# SparkFun_GPS_NEO_M9N_uFL.net
KiCad netlist of a schematic drawn in EAGLE
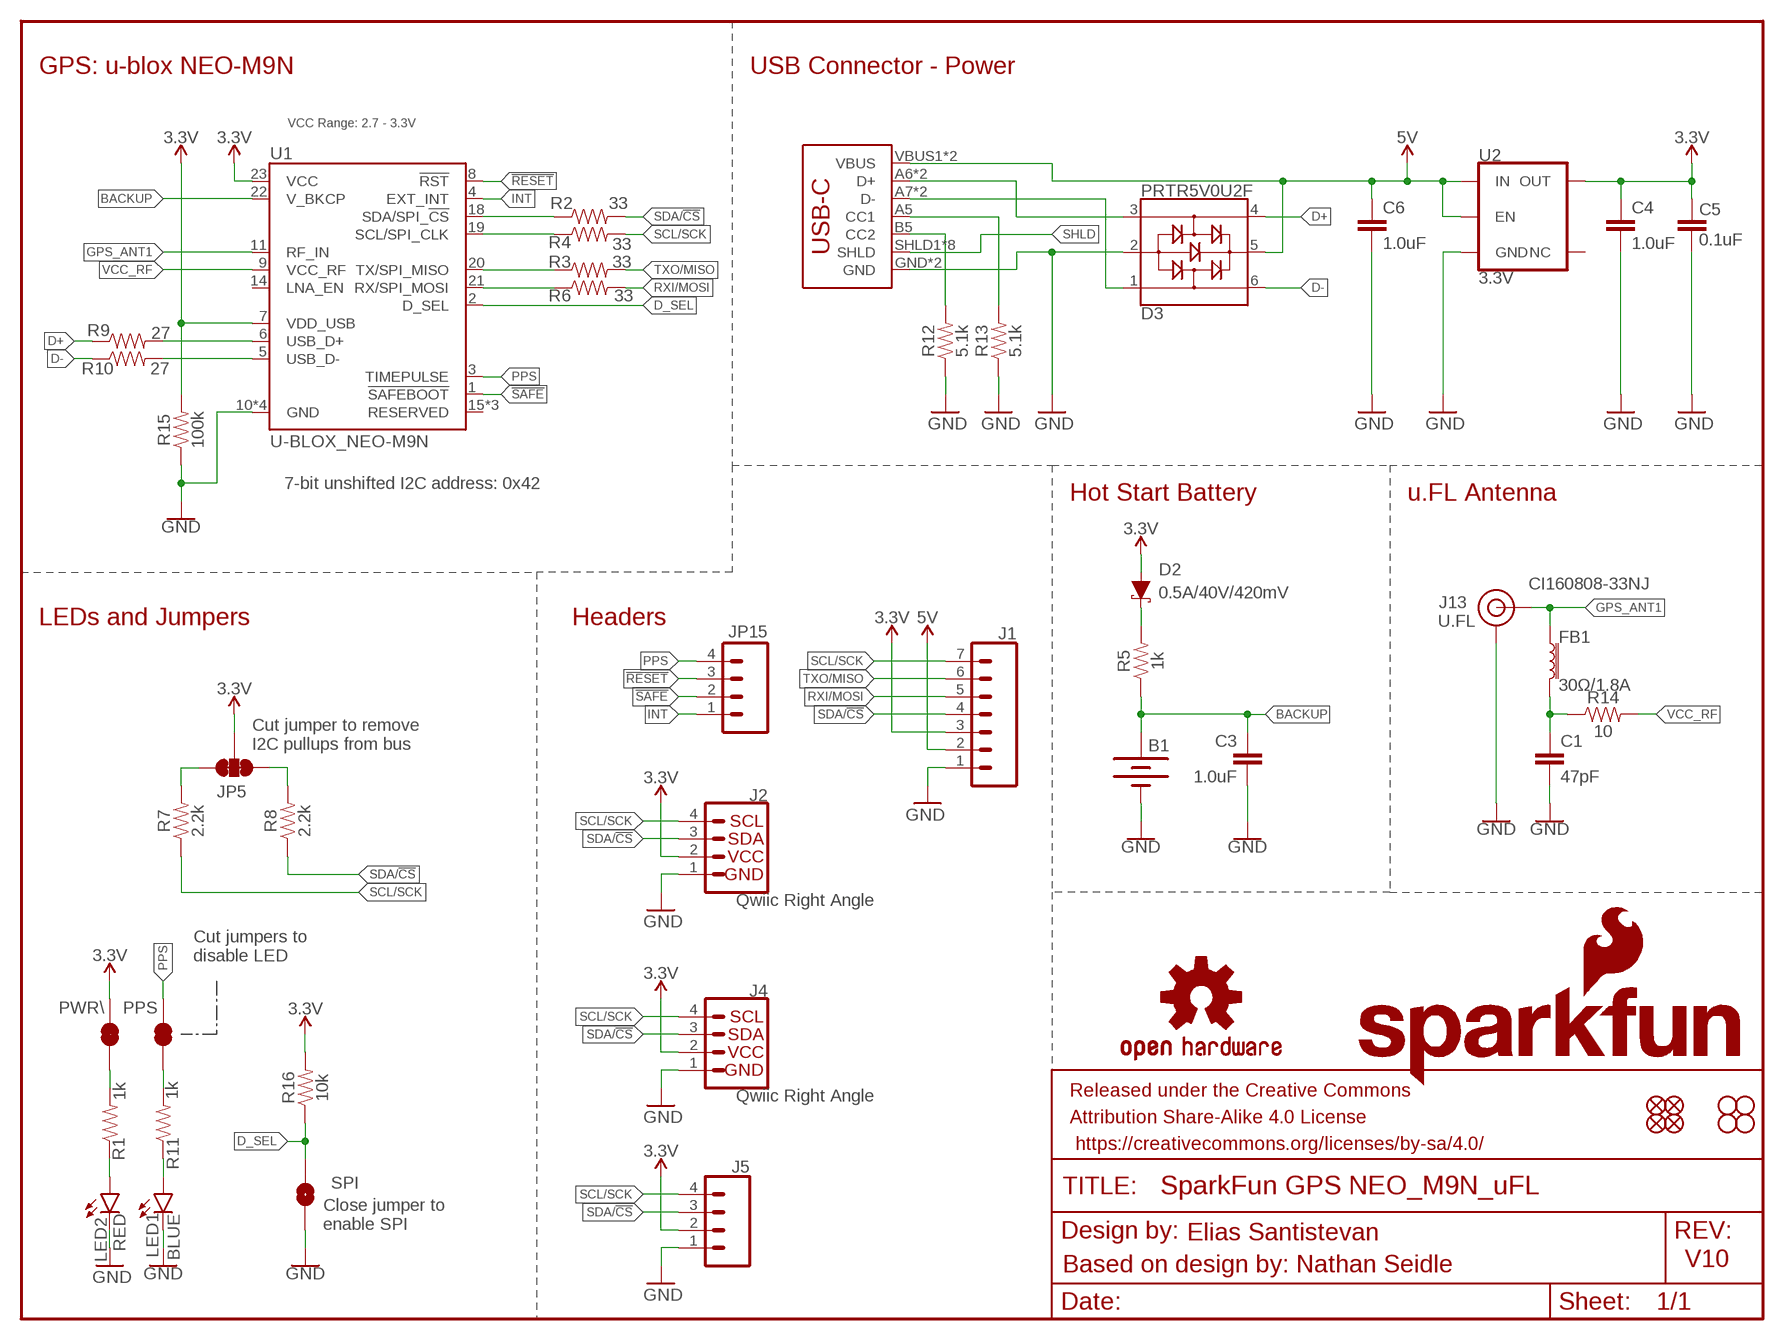
[diagram p0: schematic, sheet 1]

(export (version "E")
  (design (tool "Eeschema 10.0.6"))
  (components
    (comp (ref "B1")
      (value "6.8MM_COIN_CELL")
      (footprint "eagle-import:ML414H_IV01E")
      (libsource (lib "eagle-import") (part "ML414H_IV01E_BATTERY"))
    )
    (comp (ref "C1")
      (value "47pF")
      (footprint "eagle-import:0603")
      (libsource (lib "eagle-import") (part "47PF-0603-50V-5%"))
    )
    (comp (ref "C3")
      (value "1.0uF")
      (footprint "eagle-import:0603")
      (libsource (lib "eagle-import") (part "1.0UF-0603-16V-10%"))
    )
    (comp (ref "C4")
      (value "1.0uF")
      (footprint "eagle-import:0603")
      (libsource (lib "eagle-import") (part "1.0UF-0603-16V-10%"))
    )
    (comp (ref "C5")
      (value "0.1uF")
      (footprint "eagle-import:0603")
      (libsource (lib "eagle-import") (part "0.1UF-0603-25V-(+80/-20%)"))
    )
    (comp (ref "C6")
      (value "1.0uF")
      (footprint "eagle-import:0603")
      (libsource (lib "eagle-import") (part "1.0UF-0603-16V-10%"))
    )
    (comp (ref "D2")
      (value "0.5A/40V/420mV")
      (footprint "eagle-import:SOD-323")
      (libsource (lib "eagle-import") (part "DIODE-SCHOTTKY-PMEG4005EJ"))
    )
    (comp (ref "D3")
      (value "PRTR5V0U2F")
      (footprint "eagle-import:SOT886")
      (libsource (lib "eagle-import") (part "PRTR5V0U2F"))
    )
    (comp (ref "FB1")
      (value "30Ω/1.8A")
      (footprint "eagle-import:0603")
      (libsource (lib "eagle-import") (part "FERRITE_BEAD-0603"))
    )
    (comp (ref "FRAME1")
      (value "FRAME-LETTER")
      (footprint "eagle-import:CREATIVE_COMMONS")
      (libsource (lib "eagle-import") (part "FRAME-LETTER"))
    )
    (comp (ref "J1")
      (value "CONN_07NO_SILK")
      (footprint "eagle-import:1X07_NO_SILK")
      (libsource (lib "eagle-import") (part "CONN_07NO_SILK"))
    )
    (comp (ref "J2")
      (value "Qwiic Right Angle")
      (footprint "eagle-import:JST04_1MM_RA")
      (libsource (lib "eagle-import") (part "I2C_STANDARDQWIIC"))
    )
    (comp (ref "J3")
      (value "USB_C2-LAYER")
      (footprint "eagle-import:USB-C-16P")
      (libsource (lib "eagle-import") (part "USB_C2-LAYER"))
    )
    (comp (ref "J4")
      (value "Qwiic Right Angle")
      (footprint "eagle-import:JST04_1MM_RA")
      (libsource (lib "eagle-import") (part "I2C_STANDARDQWIIC"))
    )
    (comp (ref "J5")
      (value "CONN_041X04_NO_SILK")
      (footprint "eagle-import:1X04_NO_SILK")
      (libsource (lib "eagle-import") (part "CONN_041X04_NO_SILK"))
    )
    (comp (ref "J13")
      (value "U.FL")
      (footprint "eagle-import:U.FL")
      (libsource (lib "eagle-import") (part "U.FL2PIN"))
    )
    (comp (ref "JP5")
      (value "JUMPER-SMT_3_2-NC_TRACE_SILK")
      (footprint "eagle-import:SMT-JUMPER_3_2-NC_TRACE_SILK")
      (libsource (lib "eagle-import") (part "JUMPER-SMT_3_2-NC_TRACE_SILK"))
    )
    (comp (ref "JP15")
      (value "CONN_041X04_NO_SILK")
      (footprint "eagle-import:1X04_NO_SILK")
      (libsource (lib "eagle-import") (part "CONN_041X04_NO_SILK"))
    )
    (comp (ref "JP21")
      (value "FIDUCIALUFIDUCIAL")
      (footprint "eagle-import:MICRO-FIDUCIAL")
      (libsource (lib "eagle-import") (part "FIDUCIALUFIDUCIAL"))
    )
    (comp (ref "JP31")
      (value "STAND-OFF")
      (footprint "eagle-import:STAND-OFF")
      (libsource (lib "eagle-import") (part "STAND-OFF"))
    )
    (comp (ref "JP41")
      (value "STAND-OFF")
      (footprint "eagle-import:STAND-OFF")
      (libsource (lib "eagle-import") (part "STAND-OFF"))
    )
    (comp (ref "JP61")
      (value "FIDUCIALUFIDUCIAL")
      (footprint "eagle-import:MICRO-FIDUCIAL")
      (libsource (lib "eagle-import") (part "FIDUCIALUFIDUCIAL"))
    )
    (comp (ref "JP71")
      (value "FIDUCIALUFIDUCIAL")
      (footprint "eagle-import:MICRO-FIDUCIAL")
      (libsource (lib "eagle-import") (part "FIDUCIALUFIDUCIAL"))
    )
    (comp (ref "JP81")
      (value "FIDUCIALUFIDUCIAL")
      (footprint "eagle-import:MICRO-FIDUCIAL")
      (libsource (lib "eagle-import") (part "FIDUCIALUFIDUCIAL"))
    )
    (comp (ref "JP91")
      (value "STAND-OFF")
      (footprint "eagle-import:STAND-OFF")
      (libsource (lib "eagle-import") (part "STAND-OFF"))
    )
    (comp (ref "JP101")
      (value "STAND-OFF")
      (footprint "eagle-import:STAND-OFF")
      (libsource (lib "eagle-import") (part "STAND-OFF"))
    )
    (comp (ref "LED1")
      (value "BLUE")
      (footprint "eagle-import:LED-0603")
      (libsource (lib "eagle-import") (part "LED-BLUE0603"))
    )
    (comp (ref "LED2")
      (value "RED")
      (footprint "eagle-import:LED-0603")
      (libsource (lib "eagle-import") (part "LED-RED0603"))
    )
    (comp (ref "LOGO1")
      (value "OSHW-LOGOMINI")
      (footprint "eagle-import:OSHW-LOGO-MINI")
      (libsource (lib "eagle-import") (part "OSHW-LOGOMINI"))
    )
    (comp (ref "LOGO2")
      (value "SFE_LOGO_NAME_FLAME.1_INCH")
      (footprint "eagle-import:SFE_LOGO_NAME_FLAME_.1")
      (libsource (lib "eagle-import") (part "SFE_LOGO_NAME_FLAME.1_INCH"))
    )
    (comp (ref "PPS")
      (value "JUMPER-SMT_2_NC_TRACE_SILK")
      (footprint "eagle-import:SMT-JUMPER_2_NC_TRACE_SILK")
      (libsource (lib "eagle-import") (part "JUMPER-SMT_2_NC_TRACE_SILK"))
    )
    (comp (ref "PWR\\")
      (value "JUMPER-SMT_2_NC_TRACE_SILK")
      (footprint "eagle-import:SMT-JUMPER_2_NC_TRACE_SILK")
      (libsource (lib "eagle-import") (part "JUMPER-SMT_2_NC_TRACE_SILK"))
    )
    (comp (ref "R1")
      (value "1k")
      (footprint "eagle-import:0603")
      (libsource (lib "eagle-import") (part "1KOHM-0603-1/10W-1%"))
    )
    (comp (ref "R2")
      (value "33")
      (footprint "eagle-import:0603")
      (libsource (lib "eagle-import") (part "33OHM-0603-1/10W-1%"))
    )
    (comp (ref "R3")
      (value "33")
      (footprint "eagle-import:0603")
      (libsource (lib "eagle-import") (part "33OHM-0603-1/10W-1%"))
    )
    (comp (ref "R4")
      (value "33")
      (footprint "eagle-import:0603")
      (libsource (lib "eagle-import") (part "33OHM-0603-1/10W-1%"))
    )
    (comp (ref "R5")
      (value "1k")
      (footprint "eagle-import:0603")
      (libsource (lib "eagle-import") (part "1KOHM-0603-1/10W-1%"))
    )
    (comp (ref "R6")
      (value "33")
      (footprint "eagle-import:0603")
      (libsource (lib "eagle-import") (part "33OHM-0603-1/10W-1%"))
    )
    (comp (ref "R7")
      (value "2.2k")
      (footprint "eagle-import:0603")
      (libsource (lib "eagle-import") (part "2.2KOHM-0603-1/10W-1%"))
    )
    (comp (ref "R8")
      (value "2.2k")
      (footprint "eagle-import:0603")
      (libsource (lib "eagle-import") (part "2.2KOHM-0603-1/10W-1%"))
    )
    (comp (ref "R9")
      (value "27")
      (footprint "eagle-import:0603")
      (libsource (lib "eagle-import") (part "27OHM-0603-1/10W-1%"))
    )
    (comp (ref "R10")
      (value "27")
      (footprint "eagle-import:0603")
      (libsource (lib "eagle-import") (part "27OHM-0603-1/10W-1%"))
    )
    (comp (ref "R11")
      (value "1k")
      (footprint "eagle-import:0603")
      (libsource (lib "eagle-import") (part "1KOHM-0603-1/10W-1%"))
    )
    (comp (ref "R12")
      (value "5.1k")
      (footprint "eagle-import:0603")
      (libsource (lib "eagle-import") (part "5.1KOHM5.1KOHM-0603-1/10W-1%"))
    )
    (comp (ref "R13")
      (value "5.1k")
      (footprint "eagle-import:0603")
      (libsource (lib "eagle-import") (part "5.1KOHM5.1KOHM-0603-1/10W-1%"))
    )
    (comp (ref "R14")
      (value "10")
      (footprint "eagle-import:0603")
      (libsource (lib "eagle-import") (part "10OHM-0603-1/10W-1%"))
    )
    (comp (ref "R15")
      (value "100k")
      (footprint "eagle-import:0603")
      (libsource (lib "eagle-import") (part "100KOHM-0603-1/10W-1%"))
    )
    (comp (ref "R16")
      (value "10k")
      (footprint "eagle-import:0402")
      (libsource (lib "eagle-import") (part "10KOHM-0402-1/16W-1%"))
    )
    (comp (ref "SPI")
      (value "JUMPER-SMT_2_NO_SILK")
      (footprint "eagle-import:SMT-JUMPER_2_NO_SILK")
      (libsource (lib "eagle-import") (part "JUMPER-SMT_2_NO_SILK"))
    )
    (comp (ref "U1")
      (value "U-BLOX_NEO-M9N")
      (footprint "eagle-import:NEO-M9N")
      (libsource (lib "eagle-import") (part "U-BLOX_NEO-M9N"))
    )
    (comp (ref "U2")
      (value "3.3V")
      (footprint "eagle-import:SOT23-5")
      (libsource (lib "eagle-import") (part "V_REG_AP2112K-3.3V"))
    )
  )
  (nets
    (net (code "1") (name "/SDA{slash}~{CS}") (class "Default")
      (node (ref "J1") (pin "4") (pinfunction "4_4") (pintype "passive"))
      (node (ref "J2") (pin "3") (pinfunction "3_3") (pintype "passive"))
      (node (ref "J4") (pin "3") (pinfunction "3_3") (pintype "passive"))
      (node (ref "J5") (pin "3") (pinfunction "3_3") (pintype "passive"))
      (node (ref "R2") (pin "2") (pinfunction "2_2") (pintype "passive"))
      (node (ref "R8") (pin "1") (pinfunction "1_1") (pintype "passive"))
    )
    (net (code "2") (name "/~{RESET}") (class "Default")
      (node (ref "JP15") (pin "3") (pinfunction "3_3") (pintype "passive"))
      (node (ref "U1") (pin "8") (pinfunction "~{RST}_8") (pintype "bidirectional"))
    )
    (net (code "3") (name "/~{SAFE}") (class "Default")
      (node (ref "JP15") (pin "2") (pinfunction "2_2") (pintype "passive"))
      (node (ref "U1") (pin "1") (pinfunction "~{SAFEBOOT}_1") (pintype "bidirectional"))
    )
    (net (code "4") (name "3.3V") (class "Default")
      (node (ref "C4") (pin "1") (pinfunction "1_1") (pintype "passive"))
      (node (ref "C5") (pin "2") (pinfunction "2_2") (pintype "passive"))
      (node (ref "D2") (pin "A") (pinfunction "A_A") (pintype "passive"))
      (node (ref "J1") (pin "3") (pinfunction "3_3") (pintype "passive"))
      (node (ref "J2") (pin "2") (pinfunction "2_2") (pintype "power_in"))
      (node (ref "J4") (pin "2") (pinfunction "2_2") (pintype "power_in"))
      (node (ref "J5") (pin "2") (pinfunction "2_2") (pintype "passive"))
      (node (ref "JP5") (pin "2") (pinfunction "2_2") (pintype "passive"))
      (node (ref "PWR\\") (pin "2") (pinfunction "2_2") (pintype "passive"))
      (node (ref "R15") (pin "2") (pinfunction "2_2") (pintype "passive"))
      (node (ref "R16") (pin "2") (pinfunction "2_2") (pintype "passive"))
      (node (ref "U1") (pin "23") (pinfunction "VCC_23") (pintype "bidirectional"))
      (node (ref "U1") (pin "7") (pinfunction "VDD_USB_7") (pintype "bidirectional"))
      (node (ref "U2") (pin "5") (pinfunction "OUT_5") (pintype "passive"))
    )
    (net (code "5") (name "5V") (class "Default")
      (node (ref "C6") (pin "1") (pinfunction "1_1") (pintype "passive"))
      (node (ref "D3") (pin "5") (pinfunction "5_5") (pintype "bidirectional"))
      (node (ref "J1") (pin "2") (pinfunction "2_2") (pintype "passive"))
      (node (ref "J3") (pin "VBUS1") (pinfunction "VBUS_VBUS1") (pintype "bidirectional"))
      (node (ref "J3") (pin "VBUS2") (pinfunction "VBUS_VBUS2") (pintype "bidirectional"))
      (node (ref "U2") (pin "1") (pinfunction "IN_1") (pintype "input"))
      (node (ref "U2") (pin "3") (pinfunction "EN_3") (pintype "input"))
    )
    (net (code "6") (name "BACKUP") (class "Default")
      (node (ref "B1") (pin "+") (pinfunction "+_+") (pintype "power_in"))
      (node (ref "C3") (pin "1") (pinfunction "1_1") (pintype "passive"))
      (node (ref "R5") (pin "1") (pinfunction "1_1") (pintype "passive"))
      (node (ref "U1") (pin "22") (pinfunction "V_BKCP_22") (pintype "bidirectional"))
    )
    (net (code "7") (name "D+") (class "Default")
      (node (ref "D3") (pin "4") (pinfunction "4_4") (pintype "bidirectional"))
      (node (ref "R9") (pin "1") (pinfunction "1_1") (pintype "passive"))
    )
    (net (code "8") (name "D-") (class "Default")
      (node (ref "D3") (pin "6") (pinfunction "6_6") (pintype "bidirectional"))
      (node (ref "R10") (pin "1") (pinfunction "1_1") (pintype "passive"))
    )
    (net (code "9") (name "D_SEL") (class "Default")
      (node (ref "R16") (pin "1") (pinfunction "1_1") (pintype "passive"))
      (node (ref "SPI") (pin "2") (pinfunction "2_2") (pintype "passive"))
      (node (ref "U1") (pin "2") (pinfunction "D_SEL_2") (pintype "bidirectional"))
    )
    (net (code "10") (name "GND") (class "Default")
      (node (ref "B1") (pin "-") (pinfunction "-_-") (pintype "power_in"))
      (node (ref "C1") (pin "2") (pinfunction "2_2") (pintype "passive"))
      (node (ref "C3") (pin "2") (pinfunction "2_2") (pintype "passive"))
      (node (ref "C4") (pin "2") (pinfunction "2_2") (pintype "passive"))
      (node (ref "C5") (pin "1") (pinfunction "1_1") (pintype "passive"))
      (node (ref "C6") (pin "2") (pinfunction "2_2") (pintype "passive"))
      (node (ref "D3") (pin "2") (pinfunction "2_2") (pintype "bidirectional"))
      (node (ref "J1") (pin "1") (pinfunction "1_1") (pintype "passive"))
      (node (ref "J13") (pin "1") (pinfunction "GND_1") (pintype "bidirectional"))
      (node (ref "J13") (pin "2") (pinfunction "GND_2") (pintype "bidirectional"))
      (node (ref "J2") (pin "1") (pinfunction "1_1") (pintype "power_in"))
      (node (ref "J3") (pin "GND") (pinfunction "GND_GND") (pintype "bidirectional"))
      (node (ref "J3") (pin "GND2") (pinfunction "GND_GND2") (pintype "bidirectional"))
      (node (ref "J4") (pin "1") (pinfunction "1_1") (pintype "power_in"))
      (node (ref "J5") (pin "1") (pinfunction "1_1") (pintype "passive"))
      (node (ref "LED1") (pin "C") (pinfunction "C_C") (pintype "passive"))
      (node (ref "LED2") (pin "C") (pinfunction "C_C") (pintype "passive"))
      (node (ref "R12") (pin "1") (pinfunction "1_1") (pintype "passive"))
      (node (ref "R13") (pin "1") (pinfunction "1_1") (pintype "passive"))
      (node (ref "R15") (pin "1") (pinfunction "1_1") (pintype "passive"))
      (node (ref "SPI") (pin "1") (pinfunction "1_1") (pintype "passive"))
      (node (ref "U1") (pin "10") (pinfunction "GND_10") (pintype "bidirectional"))
      (node (ref "U1") (pin "12") (pinfunction "GND_12") (pintype "bidirectional"))
      (node (ref "U1") (pin "13") (pinfunction "GND_13") (pintype "bidirectional"))
      (node (ref "U1") (pin "24") (pinfunction "GND_24") (pintype "bidirectional"))
      (node (ref "U2") (pin "2") (pinfunction "GND_2") (pintype "input"))
    )
    (net (code "11") (name "GPS_ANT1") (class "Default")
      (node (ref "FB1") (pin "1") (pinfunction "1_1") (pintype "passive"))
      (node (ref "J13") (pin "FEED") (pinfunction "SIGNAL_FEED") (pintype "bidirectional"))
      (node (ref "U1") (pin "11") (pinfunction "RF_IN_11") (pintype "bidirectional"))
    )
    (net (code "12") (name "INT") (class "Default")
      (node (ref "JP15") (pin "1") (pinfunction "1_1") (pintype "passive"))
      (node (ref "U1") (pin "4") (pinfunction "EXT_INT_4") (pintype "bidirectional"))
    )
    (net (code "13") (name "Net-(C1-Pad1)") (class "Default")
      (node (ref "C1") (pin "1") (pinfunction "1_1") (pintype "passive"))
      (node (ref "FB1") (pin "2") (pinfunction "2_2") (pintype "passive"))
      (node (ref "R14") (pin "1") (pinfunction "1_1") (pintype "passive"))
    )
    (net (code "14") (name "Net-(D2-PadC)") (class "Default")
      (node (ref "D2") (pin "C") (pinfunction "C_C") (pintype "passive"))
      (node (ref "R5") (pin "2") (pinfunction "2_2") (pintype "passive"))
    )
    (net (code "15") (name "Net-(D3-Pad1)") (class "Default")
      (node (ref "D3") (pin "1") (pinfunction "1_1") (pintype "bidirectional"))
      (node (ref "J3") (pin "A7") (pinfunction "D-_A7") (pintype "bidirectional"))
      (node (ref "J3") (pin "B7") (pinfunction "D-_B7") (pintype "bidirectional"))
    )
    (net (code "16") (name "Net-(D3-Pad3)") (class "Default")
      (node (ref "D3") (pin "3") (pinfunction "3_3") (pintype "bidirectional"))
      (node (ref "J3") (pin "A6") (pinfunction "D+_A6") (pintype "bidirectional"))
      (node (ref "J3") (pin "B6") (pinfunction "D+_B6") (pintype "bidirectional"))
    )
    (net (code "17") (name "Net-(J3-CC1)") (class "Default")
      (node (ref "J3") (pin "A5") (pinfunction "CC1_A5") (pintype "bidirectional"))
      (node (ref "R13") (pin "2") (pinfunction "2_2") (pintype "passive"))
    )
    (net (code "18") (name "Net-(J3-CC2)") (class "Default")
      (node (ref "J3") (pin "B5") (pinfunction "CC2_B5") (pintype "bidirectional"))
      (node (ref "R12") (pin "2") (pinfunction "2_2") (pintype "passive"))
    )
    (net (code "19") (name "Net-(JP5-Pad1)") (class "Default")
      (node (ref "JP5") (pin "1") (pinfunction "1_1") (pintype "passive"))
      (node (ref "R8") (pin "2") (pinfunction "2_2") (pintype "passive"))
    )
    (net (code "20") (name "Net-(JP5-Pad3)") (class "Default")
      (node (ref "JP5") (pin "3") (pinfunction "3_3") (pintype "passive"))
      (node (ref "R7") (pin "2") (pinfunction "2_2") (pintype "passive"))
    )
    (net (code "21") (name "Net-(LED1-PadA)") (class "Default")
      (node (ref "LED1") (pin "A") (pinfunction "A_A") (pintype "passive"))
      (node (ref "R11") (pin "1") (pinfunction "1_1") (pintype "passive"))
    )
    (net (code "22") (name "Net-(LED2-PadA)") (class "Default")
      (node (ref "LED2") (pin "A") (pinfunction "A_A") (pintype "passive"))
      (node (ref "R1") (pin "1") (pinfunction "1_1") (pintype "passive"))
    )
    (net (code "23") (name "Net-(PPS-Pad1)") (class "Default")
      (node (ref "PPS") (pin "1") (pinfunction "1_1") (pintype "passive"))
      (node (ref "R11") (pin "2") (pinfunction "2_2") (pintype "passive"))
    )
    (net (code "24") (name "Net-(PWR\\-Pad1)") (class "Default")
      (node (ref "PWR\\") (pin "1") (pinfunction "1_1") (pintype "passive"))
      (node (ref "R1") (pin "2") (pinfunction "2_2") (pintype "passive"))
    )
    (net (code "25") (name "Net-(U1-RX{slash}SPI_MOSI)") (class "Default")
      (node (ref "R6") (pin "1") (pinfunction "1_1") (pintype "passive"))
      (node (ref "U1") (pin "21") (pinfunction "RX/SPI_MOSI_21") (pintype "bidirectional"))
    )
    (net (code "26") (name "Net-(U1-SCL{slash}SPI_CLK)") (class "Default")
      (node (ref "R4") (pin "1") (pinfunction "1_1") (pintype "passive"))
      (node (ref "U1") (pin "19") (pinfunction "SCL/SPI_CLK_19") (pintype "bidirectional"))
    )
    (net (code "27") (name "Net-(U1-SDA{slash}SPI_~{CS})") (class "Default")
      (node (ref "R2") (pin "1") (pinfunction "1_1") (pintype "passive"))
      (node (ref "U1") (pin "18") (pinfunction "SDA/SPI_~{CS}_18") (pintype "bidirectional"))
    )
    (net (code "28") (name "Net-(U1-TX{slash}SPI_MISO)") (class "Default")
      (node (ref "R3") (pin "1") (pinfunction "1_1") (pintype "passive"))
      (node (ref "U1") (pin "20") (pinfunction "TX/SPI_MISO_20") (pintype "bidirectional"))
    )
    (net (code "29") (name "Net-(U1-USB_D+)") (class "Default")
      (node (ref "R9") (pin "2") (pinfunction "2_2") (pintype "passive"))
      (node (ref "U1") (pin "6") (pinfunction "USB_D+_6") (pintype "bidirectional"))
    )
    (net (code "30") (name "Net-(U1-USB_D-)") (class "Default")
      (node (ref "R10") (pin "2") (pinfunction "2_2") (pintype "passive"))
      (node (ref "U1") (pin "5") (pinfunction "USB_D-_5") (pintype "bidirectional"))
    )
    (net (code "31") (name "PPS") (class "Default")
      (node (ref "JP15") (pin "4") (pinfunction "4_4") (pintype "passive"))
      (node (ref "PPS") (pin "2") (pinfunction "2_2") (pintype "passive"))
      (node (ref "U1") (pin "3") (pinfunction "TIMEPULSE_3") (pintype "bidirectional"))
    )
    (net (code "32") (name "RXI{slash}MOSI") (class "Default")
      (node (ref "J1") (pin "5") (pinfunction "5_5") (pintype "passive"))
      (node (ref "R6") (pin "2") (pinfunction "2_2") (pintype "passive"))
    )
    (net (code "33") (name "SCL{slash}SCK") (class "Default")
      (node (ref "J1") (pin "7") (pinfunction "7_7") (pintype "passive"))
      (node (ref "J2") (pin "4") (pinfunction "4_4") (pintype "passive"))
      (node (ref "J4") (pin "4") (pinfunction "4_4") (pintype "passive"))
      (node (ref "J5") (pin "4") (pinfunction "4_4") (pintype "passive"))
      (node (ref "R4") (pin "2") (pinfunction "2_2") (pintype "passive"))
      (node (ref "R7") (pin "1") (pinfunction "1_1") (pintype "passive"))
    )
    (net (code "34") (name "SHLD") (class "Default")
      (node (ref "J3") (pin "SHLD1") (pinfunction "SHLD_SHLD1") (pintype "bidirectional"))
      (node (ref "J3") (pin "SHLD2") (pinfunction "SHLD_SHLD2") (pintype "bidirectional"))
      (node (ref "J3") (pin "SHLD3") (pinfunction "SHLD_SHLD3") (pintype "bidirectional"))
      (node (ref "J3") (pin "SHLD4") (pinfunction "SHLD_SHLD4") (pintype "bidirectional"))
      (node (ref "J3") (pin "SHLD5") (pinfunction "SHLD_SHLD5") (pintype "bidirectional"))
      (node (ref "J3") (pin "SHLD6") (pinfunction "SHLD_SHLD6") (pintype "bidirectional"))
      (node (ref "J3") (pin "SHLD7") (pinfunction "SHLD_SHLD7") (pintype "bidirectional"))
      (node (ref "J3") (pin "SHLD8") (pinfunction "SHLD_SHLD8") (pintype "bidirectional"))
    )
    (net (code "35") (name "TXO{slash}MISO") (class "Default")
      (node (ref "J1") (pin "6") (pinfunction "6_6") (pintype "passive"))
      (node (ref "R3") (pin "2") (pinfunction "2_2") (pintype "passive"))
    )
    (net (code "36") (name "VCC_RF") (class "Default")
      (node (ref "R14") (pin "2") (pinfunction "2_2") (pintype "passive"))
      (node (ref "U1") (pin "9") (pinfunction "VCC_RF_9") (pintype "bidirectional"))
    )
    (net (code "37") (name "unconnected-(U1-LNA_EN-Pad14)") (class "Default")
      (node (ref "U1") (pin "14") (pinfunction "LNA_EN_14") (pintype "bidirectional"))
    )
    (net (code "38") (name "unconnected-(U1-RESERVED-Pad15)") (class "Default")
      (node (ref "U1") (pin "15") (pinfunction "RESERVED_15") (pintype "no_connect"))
    )
    (net (code "39") (name "unconnected-(U1-RESERVED-Pad16)") (class "Default")
      (node (ref "U1") (pin "16") (pinfunction "RESERVED_16") (pintype "no_connect"))
    )
    (net (code "40") (name "unconnected-(U1-RESERVED-Pad17)") (class "Default")
      (node (ref "U1") (pin "17") (pinfunction "RESERVED_17") (pintype "no_connect"))
    )
    (net (code "41") (name "unconnected-(U2-NC-Pad4)") (class "Default")
      (node (ref "U2") (pin "4") (pinfunction "NC_4") (pintype "no_connect"))
    )
  )
)
